# USB-CONN.net
KiCad netlist of a schematic drawn in Altium Designer
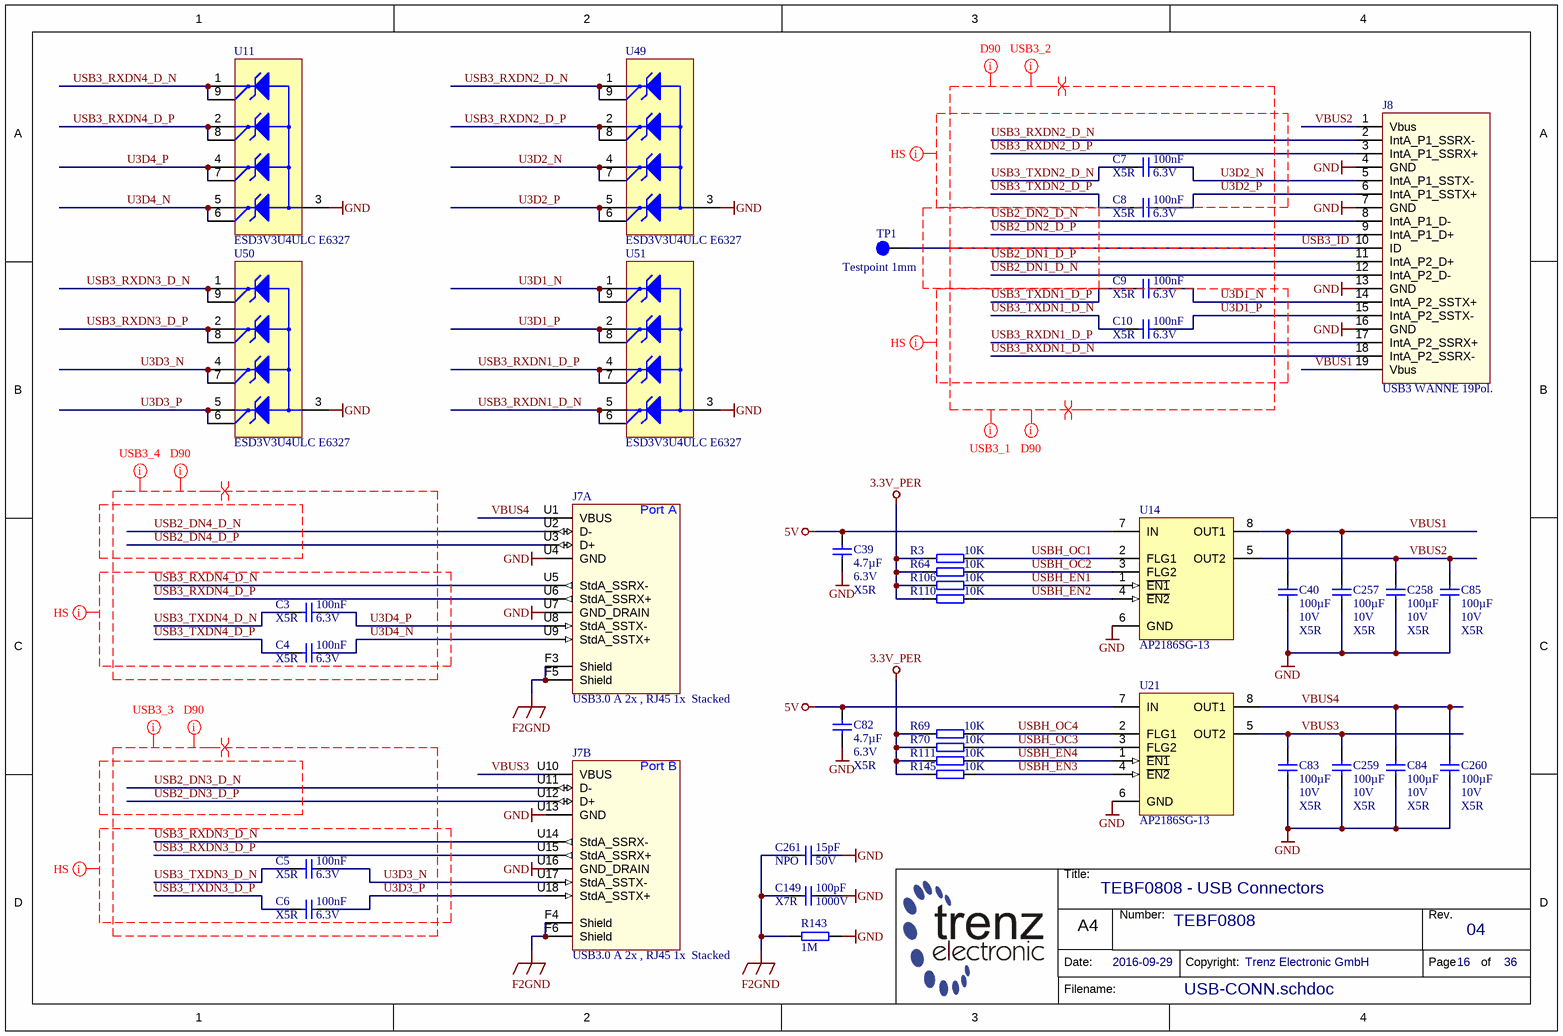
[diagram p0: USB-CONN.schdoc]

(export (version "E")
  (design (tool "Eeschema 10.0.6"))
  (components
    (comp (ref "C3")
      (value "100nF")
      (footprint "CAPC0603X33N")
      (description "KON 100nF 6.3V X5R SMD 10%")
      (fields
        (field (name "VOLTAGE") "6.3V")
        (field (name "TECHNOLOGY") "X5R")
        (field (name "TOLERANCE") "10%")
      )
      (libsource (lib "TE") (part "CAP-NP"))
    )
    (comp (ref "C4")
      (value "100nF")
      (footprint "CAPC0603X33N")
      (description "KON 100nF 6.3V X5R SMD 10%")
      (fields
        (field (name "VOLTAGE") "6.3V")
        (field (name "TECHNOLOGY") "X5R")
        (field (name "TOLERANCE") "10%")
      )
      (libsource (lib "TE") (part "CAP-NP"))
    )
    (comp (ref "C5")
      (value "100nF")
      (footprint "CAPC0603X33N")
      (description "KON 100nF 6.3V X5R SMD 10%")
      (fields
        (field (name "VOLTAGE") "6.3V")
        (field (name "TECHNOLOGY") "X5R")
        (field (name "TOLERANCE") "10%")
      )
      (libsource (lib "TE") (part "CAP-NP"))
    )
    (comp (ref "C6")
      (value "100nF")
      (footprint "CAPC0603X33N")
      (description "KON 100nF 6.3V X5R SMD 10%")
      (fields
        (field (name "VOLTAGE") "6.3V")
        (field (name "TECHNOLOGY") "X5R")
        (field (name "TOLERANCE") "10%")
      )
      (libsource (lib "TE") (part "CAP-NP"))
    )
    (comp (ref "C7")
      (value "100nF")
      (footprint "CAPC0603X33N")
      (description "KON 100nF 6.3V X5R SMD 10%")
      (fields
        (field (name "VOLTAGE") "6.3V")
        (field (name "TECHNOLOGY") "X5R")
        (field (name "TOLERANCE") "10%")
      )
      (libsource (lib "TE") (part "CAP-NP"))
    )
    (comp (ref "C8")
      (value "100nF")
      (footprint "CAPC0603X33N")
      (description "KON 100nF 6.3V X5R SMD 10%")
      (fields
        (field (name "VOLTAGE") "6.3V")
        (field (name "TECHNOLOGY") "X5R")
        (field (name "TOLERANCE") "10%")
      )
      (libsource (lib "TE") (part "CAP-NP"))
    )
    (comp (ref "C9")
      (value "100nF")
      (footprint "CAPC0603X33N")
      (description "KON 100nF 6.3V X5R SMD 10%")
      (fields
        (field (name "VOLTAGE") "6.3V")
        (field (name "TECHNOLOGY") "X5R")
        (field (name "TOLERANCE") "10%")
      )
      (libsource (lib "TE") (part "CAP-NP"))
    )
    (comp (ref "C10")
      (value "100nF")
      (footprint "CAPC0603X33N")
      (description "KON 100nF 6.3V X5R SMD 10%")
      (fields
        (field (name "VOLTAGE") "6.3V")
        (field (name "TECHNOLOGY") "X5R")
        (field (name "TOLERANCE") "10%")
      )
      (libsource (lib "TE") (part "CAP-NP"))
    )
    (comp (ref "C39")
      (value "4.7µF")
      (footprint "CAPC1005X60N")
      (description "KON 4.7µF 6.3V X5R SMD 20%")
      (fields
        (field (name "VOLTAGE") "6.3V")
        (field (name "TECHNOLOGY") "X5R")
        (field (name "TOLERANCE") "20%")
      )
      (libsource (lib "TE") (part "CAP-NP"))
    )
    (comp (ref "C40")
      (value "100µF")
      (footprint "CAPC3216X180N")
      (description "KON 100µF 10V X5R SMD 20%")
      (fields
        (field (name "VOLTAGE") "10V")
        (field (name "TECHNOLOGY") "X5R")
        (field (name "TOLERANCE") "20%")
      )
      (libsource (lib "TE") (part "CAP-NP"))
    )
    (comp (ref "C82")
      (value "4.7µF")
      (footprint "CAPC1005X60N")
      (description "KON 4.7µF 6.3V X5R SMD 20%")
      (fields
        (field (name "VOLTAGE") "6.3V")
        (field (name "TECHNOLOGY") "X5R")
        (field (name "TOLERANCE") "20%")
      )
      (libsource (lib "TE") (part "CAP-NP"))
    )
    (comp (ref "C83")
      (value "100µF")
      (footprint "CAPC3216X180N")
      (description "KON 100µF 10V X5R SMD 20%")
      (fields
        (field (name "VOLTAGE") "10V")
        (field (name "TECHNOLOGY") "X5R")
        (field (name "TOLERANCE") "20%")
      )
      (libsource (lib "TE") (part "CAP-NP"))
    )
    (comp (ref "C84")
      (value "100µF")
      (footprint "CAPC3216X180N")
      (description "KON 100µF 10V X5R SMD 20%")
      (fields
        (field (name "VOLTAGE") "10V")
        (field (name "TECHNOLOGY") "X5R")
        (field (name "TOLERANCE") "20%")
      )
      (libsource (lib "TE") (part "CAP-NP"))
    )
    (comp (ref "C85")
      (value "100µF")
      (footprint "CAPC3216X180N")
      (description "KON 100µF 10V X5R SMD 20%")
      (fields
        (field (name "VOLTAGE") "10V")
        (field (name "TECHNOLOGY") "X5R")
        (field (name "TOLERANCE") "20%")
      )
      (libsource (lib "TE") (part "CAP-NP"))
    )
    (comp (ref "C149")
      (value "100pF")
      (footprint "CAPC3216X180N")
      (description "KON 100pF 1000V X7R 10%")
      (fields
        (field (name "VOLTAGE") "X7R")
        (field (name "TECHNOLOGY") "1000V")
        (field (name "TOLERANCE") "10%")
      )
      (libsource (lib "TE") (part "CAP-NP"))
    )
    (comp (ref "C257")
      (value "100µF")
      (footprint "CAPC3216X180N")
      (description "KON 100µF 10V X5R SMD 20%")
      (fields
        (field (name "VOLTAGE") "10V")
        (field (name "TECHNOLOGY") "X5R")
        (field (name "TOLERANCE") "20%")
      )
      (libsource (lib "TE") (part "CAP-NP"))
    )
    (comp (ref "C258")
      (value "100µF")
      (footprint "CAPC3216X180N")
      (description "KON 100µF 10V X5R SMD 20%")
      (fields
        (field (name "VOLTAGE") "10V")
        (field (name "TECHNOLOGY") "X5R")
        (field (name "TOLERANCE") "20%")
      )
      (libsource (lib "TE") (part "CAP-NP"))
    )
    (comp (ref "C259")
      (value "100µF")
      (footprint "CAPC3216X180N")
      (description "KON 100µF 10V X5R SMD 20%")
      (fields
        (field (name "VOLTAGE") "10V")
        (field (name "TECHNOLOGY") "X5R")
        (field (name "TOLERANCE") "20%")
      )
      (libsource (lib "TE") (part "CAP-NP"))
    )
    (comp (ref "C260")
      (value "100µF")
      (footprint "CAPC3216X180N")
      (description "KON 100µF 10V X5R SMD 20%")
      (fields
        (field (name "VOLTAGE") "10V")
        (field (name "TECHNOLOGY") "X5R")
        (field (name "TOLERANCE") "20%")
      )
      (libsource (lib "TE") (part "CAP-NP"))
    )
    (comp (ref "C261")
      (value "15pF")
      (footprint "CAPC1005X55N")
      (description "KON 15pF NPO 50V SMD")
      (fields (field (name "VOLTAGE") "50V") (field (name "TECHNOLOGY") "NPO"))
      (libsource (lib "TE") (part "CAP-NP"))
    )
    (comp (ref "J7")
      (value "USB3.0 A 2x , RJ45 1x  Stacked")
      (footprint "7497110616")
      (libsource (lib "TE") (part "7497110616"))
    )
    (comp (ref "J8")
      (value "USB3 WANNE 19Pol.")
      (footprint "WANNE2mm2R-19_Intel_USB")
      (description "Stiftleiste USB3 Wanne 19polig 0°")
      (libsource (lib "TE") (part "USB3_ICC_A"))
    )
    (comp (ref "R3")
      (value "10K")
      (footprint "RESC1005X40N")
      (description "WID SMD 10K 1% 0,063W")
      (fields (field (name "TOLERANCE") "1%"))
      (libsource (lib "TE") (part "RES"))
    )
    (comp (ref "R64")
      (value "10K")
      (footprint "RESC1005X40N")
      (description "WID SMD 10K 1% 0,063W")
      (fields (field (name "TOLERANCE") "1%"))
      (libsource (lib "TE") (part "RES"))
    )
    (comp (ref "R69")
      (value "10K")
      (footprint "RESC1005X40N")
      (description "WID SMD 10K 1% 0,063W")
      (fields (field (name "TOLERANCE") "1%"))
      (libsource (lib "TE") (part "RES"))
    )
    (comp (ref "R70")
      (value "10K")
      (footprint "RESC1005X40N")
      (description "WID SMD 10K 1% 0,063W")
      (fields (field (name "TOLERANCE") "1%"))
      (libsource (lib "TE") (part "RES"))
    )
    (comp (ref "R106")
      (value "10K")
      (footprint "RESC1005X40N")
      (description "WID SMD 10K 1% 0,063W")
      (fields (field (name "TOLERANCE") "1%"))
      (libsource (lib "TE") (part "RES"))
    )
    (comp (ref "R110")
      (value "10K")
      (footprint "RESC1005X40N")
      (description "WID SMD 10K 1% 0,063W")
      (fields (field (name "TOLERANCE") "1%"))
      (libsource (lib "TE") (part "RES"))
    )
    (comp (ref "R111")
      (value "10K")
      (footprint "RESC1005X40N")
      (description "WID SMD 10K 1% 0,063W")
      (fields (field (name "TOLERANCE") "1%"))
      (libsource (lib "TE") (part "RES"))
    )
    (comp (ref "R143")
      (value "1M")
      (footprint "RESC3216X65N")
      (description "WID SMD 1M 5% 0,25W")
      (fields (field (name "TOLERANCE") "5%"))
      (libsource (lib "TE") (part "RES"))
    )
    (comp (ref "R145")
      (value "10K")
      (footprint "RESC1005X40N")
      (description "WID SMD 10K 1% 0,063W")
      (fields (field (name "TOLERANCE") "1%"))
      (libsource (lib "TE") (part "RES"))
    )
    (comp (ref "TP1") (value "Testpoint 1mm") (footprint "TP_1mm") (libsource (lib "TE") (part "TP")))
    (comp (ref "U11")
      (value "ESD3V3U4ULC E6327")
      (footprint "TSLP-9-1")
      (description "TVS UL Cap. 4xIOs ESD 3.3V")
      (libsource (lib "TE") (part "ESD3V3U4ULC"))
    )
    (comp (ref "U14")
      (value "AP2186SG-13")
      (footprint "SOIC127P600X175-8N")
      (libsource (lib "TE") (part "AP2186"))
    )
    (comp (ref "U21")
      (value "AP2186SG-13")
      (footprint "SOIC127P600X175-8N")
      (libsource (lib "TE") (part "AP2186"))
    )
    (comp (ref "U49")
      (value "ESD3V3U4ULC E6327")
      (footprint "TSLP-9-1")
      (description "TVS UL Cap. 4xIOs ESD 3.3V")
      (libsource (lib "TE") (part "ESD3V3U4ULC"))
    )
    (comp (ref "U50")
      (value "ESD3V3U4ULC E6327")
      (footprint "TSLP-9-1")
      (description "TVS UL Cap. 4xIOs ESD 3.3V")
      (libsource (lib "TE") (part "ESD3V3U4ULC"))
    )
    (comp (ref "U51")
      (value "ESD3V3U4ULC E6327")
      (footprint "TSLP-9-1")
      (description "TVS UL Cap. 4xIOs ESD 3.3V")
      (libsource (lib "TE") (part "ESD3V3U4ULC"))
    )
  )
  (nets
    (net (code "1") (name "/U3D1_N") (class "Default")
      (node (ref "C9") (pin "2") (pinfunction "2_2") (pintype "passive"))
      (node (ref "J8") (pin "14") (pinfunction "IntA_P2_SSTX+_14") (pintype "passive"))
      (node (ref "U51") (pin "1") (pinfunction "1_1") (pintype "passive"))
      (node (ref "U51") (pin "9") (pinfunction "9_9") (pintype "passive"))
    )
    (net (code "2") (name "/U3D1_P") (class "Default")
      (node (ref "C10") (pin "2") (pinfunction "2_2") (pintype "passive"))
      (node (ref "J8") (pin "15") (pinfunction "IntA_P2_SSTX-_15") (pintype "passive"))
      (node (ref "U51") (pin "2") (pinfunction "2_2") (pintype "passive"))
      (node (ref "U51") (pin "8") (pinfunction "8_8") (pintype "passive"))
    )
    (net (code "3") (name "/U3D2_N") (class "Default")
      (node (ref "C7") (pin "2") (pinfunction "2_2") (pintype "passive"))
      (node (ref "J8") (pin "5") (pinfunction "IntA_P1_SSTX-_5") (pintype "passive"))
      (node (ref "U49") (pin "4") (pinfunction "4_4") (pintype "passive"))
      (node (ref "U49") (pin "7") (pinfunction "7_7") (pintype "passive"))
    )
    (net (code "4") (name "/U3D2_P") (class "Default")
      (node (ref "C8") (pin "2") (pinfunction "2_2") (pintype "passive"))
      (node (ref "J8") (pin "6") (pinfunction "IntA_P1_SSTX+_6") (pintype "passive"))
      (node (ref "U49") (pin "5") (pinfunction "5_5") (pintype "passive"))
      (node (ref "U49") (pin "6") (pinfunction "6_6") (pintype "passive"))
    )
    (net (code "5") (name "/U3D3_N") (class "Default")
      (node (ref "C5") (pin "2") (pinfunction "2_2") (pintype "passive"))
      (node (ref "J7") (pin "U17") (pinfunction "StdA_SSTX-_U17") (pintype "input"))
      (node (ref "U50") (pin "4") (pinfunction "4_4") (pintype "passive"))
      (node (ref "U50") (pin "7") (pinfunction "7_7") (pintype "passive"))
    )
    (net (code "6") (name "/U3D3_P") (class "Default")
      (node (ref "C6") (pin "2") (pinfunction "2_2") (pintype "passive"))
      (node (ref "J7") (pin "U18") (pinfunction "StdA_SSTX+_U18") (pintype "input"))
      (node (ref "U50") (pin "5") (pinfunction "5_5") (pintype "passive"))
      (node (ref "U50") (pin "6") (pinfunction "6_6") (pintype "passive"))
    )
    (net (code "7") (name "/U3D4_N") (class "Default")
      (node (ref "C4") (pin "2") (pinfunction "2_2") (pintype "passive"))
      (node (ref "J7") (pin "U9") (pinfunction "StdA_SSTX+_U9") (pintype "input"))
      (node (ref "U11") (pin "5") (pinfunction "5_5") (pintype "passive"))
      (node (ref "U11") (pin "6") (pinfunction "6_6") (pintype "passive"))
    )
    (net (code "8") (name "/U3D4_P") (class "Default")
      (node (ref "C3") (pin "2") (pinfunction "2_2") (pintype "passive"))
      (node (ref "J7") (pin "U8") (pinfunction "StdA_SSTX-_U8") (pintype "input"))
      (node (ref "U11") (pin "4") (pinfunction "4_4") (pintype "passive"))
      (node (ref "U11") (pin "7") (pinfunction "7_7") (pintype "passive"))
    )
    (net (code "9") (name "/USB2_DN1_D_N") (class "Default")
      (node (ref "J8") (pin "12") (pinfunction "IntA_P2_D-_12") (pintype "passive"))
    )
    (net (code "10") (name "/USB2_DN1_D_P") (class "Default")
      (node (ref "J8") (pin "11") (pinfunction "IntA_P2_D+_11") (pintype "passive"))
    )
    (net (code "11") (name "/USB2_DN2_D_N") (class "Default")
      (node (ref "J8") (pin "8") (pinfunction "IntA_P1_D-_8") (pintype "passive"))
    )
    (net (code "12") (name "/USB2_DN2_D_P") (class "Default")
      (node (ref "J8") (pin "9") (pinfunction "IntA_P1_D+_9") (pintype "passive"))
    )
    (net (code "13") (name "/USB2_DN3_D_N") (class "Default")
      (node (ref "J7") (pin "U11") (pinfunction "D-_U11") (pintype "bidirectional"))
    )
    (net (code "14") (name "/USB2_DN3_D_P") (class "Default")
      (node (ref "J7") (pin "U12") (pinfunction "D+_U12") (pintype "bidirectional"))
    )
    (net (code "15") (name "/USB2_DN4_D_N") (class "Default")
      (node (ref "J7") (pin "U2") (pinfunction "D-_U2") (pintype "bidirectional"))
    )
    (net (code "16") (name "/USB2_DN4_D_P") (class "Default")
      (node (ref "J7") (pin "U3") (pinfunction "D+_U3") (pintype "bidirectional"))
    )
    (net (code "17") (name "/USB3_ID") (class "Default")
      (node (ref "J8") (pin "10") (pinfunction "ID_10") (pintype "passive"))
      (node (ref "TP1") (pin "1") (pintype "passive"))
    )
    (net (code "18") (name "/USB3_RXDN1_D_N") (class "Default")
      (node (ref "J8") (pin "18") (pinfunction "IntA_P2_SSRX-_18") (pintype "passive"))
      (node (ref "U51") (pin "5") (pinfunction "5_5") (pintype "passive"))
      (node (ref "U51") (pin "6") (pinfunction "6_6") (pintype "passive"))
    )
    (net (code "19") (name "/USB3_RXDN1_D_P") (class "Default")
      (node (ref "J8") (pin "17") (pinfunction "IntA_P2_SSRX+_17") (pintype "passive"))
      (node (ref "U51") (pin "4") (pinfunction "4_4") (pintype "passive"))
      (node (ref "U51") (pin "7") (pinfunction "7_7") (pintype "passive"))
    )
    (net (code "20") (name "/USB3_RXDN2_D_N") (class "Default")
      (node (ref "J8") (pin "2") (pinfunction "IntA_P1_SSRX-_2") (pintype "passive"))
      (node (ref "U49") (pin "1") (pinfunction "1_1") (pintype "passive"))
      (node (ref "U49") (pin "9") (pinfunction "9_9") (pintype "passive"))
    )
    (net (code "21") (name "/USB3_RXDN2_D_P") (class "Default")
      (node (ref "J8") (pin "3") (pinfunction "IntA_P1_SSRX+_3") (pintype "passive"))
      (node (ref "U49") (pin "2") (pinfunction "2_2") (pintype "passive"))
      (node (ref "U49") (pin "8") (pinfunction "8_8") (pintype "passive"))
    )
    (net (code "22") (name "/USB3_RXDN3_D_N") (class "Default")
      (node (ref "J7") (pin "U14") (pinfunction "StdA_SSRX-_U14") (pintype "output"))
      (node (ref "U50") (pin "1") (pinfunction "1_1") (pintype "passive"))
      (node (ref "U50") (pin "9") (pinfunction "9_9") (pintype "passive"))
    )
    (net (code "23") (name "/USB3_RXDN3_D_P") (class "Default")
      (node (ref "J7") (pin "U15") (pinfunction "StdA_SSRX+_U15") (pintype "output"))
      (node (ref "U50") (pin "2") (pinfunction "2_2") (pintype "passive"))
      (node (ref "U50") (pin "8") (pinfunction "8_8") (pintype "passive"))
    )
    (net (code "24") (name "/USB3_RXDN4_D_N") (class "Default")
      (node (ref "J7") (pin "U5") (pinfunction "StdA_SSRX-_U5") (pintype "output"))
      (node (ref "U11") (pin "1") (pinfunction "1_1") (pintype "passive"))
      (node (ref "U11") (pin "9") (pinfunction "9_9") (pintype "passive"))
    )
    (net (code "25") (name "/USB3_RXDN4_D_P") (class "Default")
      (node (ref "J7") (pin "U6") (pinfunction "StdA_SSRX+_U6") (pintype "output"))
      (node (ref "U11") (pin "2") (pinfunction "2_2") (pintype "passive"))
      (node (ref "U11") (pin "8") (pinfunction "8_8") (pintype "passive"))
    )
    (net (code "26") (name "/USB3_TXDN1_D_N") (class "Default")
      (node (ref "C10") (pin "1") (pinfunction "1_1") (pintype "passive"))
    )
    (net (code "27") (name "/USB3_TXDN1_D_P") (class "Default")
      (node (ref "C9") (pin "1") (pinfunction "1_1") (pintype "passive"))
    )
    (net (code "28") (name "/USB3_TXDN2_D_N") (class "Default")
      (node (ref "C7") (pin "1") (pinfunction "1_1") (pintype "passive"))
    )
    (net (code "29") (name "/USB3_TXDN2_D_P") (class "Default")
      (node (ref "C8") (pin "1") (pinfunction "1_1") (pintype "passive"))
    )
    (net (code "30") (name "/USB3_TXDN3_D_N") (class "Default")
      (node (ref "C5") (pin "1") (pinfunction "1_1") (pintype "passive"))
    )
    (net (code "31") (name "/USB3_TXDN3_D_P") (class "Default")
      (node (ref "C6") (pin "1") (pinfunction "1_1") (pintype "passive"))
    )
    (net (code "32") (name "/USB3_TXDN4_D_N") (class "Default")
      (node (ref "C3") (pin "1") (pinfunction "1_1") (pintype "passive"))
    )
    (net (code "33") (name "/USB3_TXDN4_D_P") (class "Default")
      (node (ref "C4") (pin "1") (pinfunction "1_1") (pintype "passive"))
    )
    (net (code "34") (name "/USBH_EN1") (class "Default")
      (node (ref "R106") (pin "2") (pinfunction "2_2") (pintype "passive"))
      (node (ref "U14") (pin "1") (pinfunction "~{EN1}_1") (pintype "input"))
    )
    (net (code "35") (name "/USBH_EN2") (class "Default")
      (node (ref "R110") (pin "2") (pinfunction "2_2") (pintype "passive"))
      (node (ref "U14") (pin "4") (pinfunction "~{EN2}_4") (pintype "input"))
    )
    (net (code "36") (name "/USBH_EN3") (class "Default")
      (node (ref "R145") (pin "2") (pinfunction "2_2") (pintype "passive"))
      (node (ref "U21") (pin "4") (pinfunction "~{EN2}_4") (pintype "input"))
    )
    (net (code "37") (name "/USBH_EN4") (class "Default")
      (node (ref "R111") (pin "2") (pinfunction "2_2") (pintype "passive"))
      (node (ref "U21") (pin "1") (pinfunction "~{EN1}_1") (pintype "input"))
    )
    (net (code "38") (name "/USBH_OC1") (class "Default")
      (node (ref "R3") (pin "2") (pinfunction "2_2") (pintype "passive"))
      (node (ref "U14") (pin "2") (pinfunction "FLG1_2") (pintype "passive"))
    )
    (net (code "39") (name "/USBH_OC2") (class "Default")
      (node (ref "R64") (pin "2") (pinfunction "2_2") (pintype "passive"))
      (node (ref "U14") (pin "3") (pinfunction "FLG2_3") (pintype "passive"))
    )
    (net (code "40") (name "/USBH_OC3") (class "Default")
      (node (ref "R70") (pin "2") (pinfunction "2_2") (pintype "passive"))
      (node (ref "U21") (pin "3") (pinfunction "FLG2_3") (pintype "passive"))
    )
    (net (code "41") (name "/USBH_OC4") (class "Default")
      (node (ref "R69") (pin "2") (pinfunction "2_2") (pintype "passive"))
      (node (ref "U21") (pin "2") (pinfunction "FLG1_2") (pintype "passive"))
    )
    (net (code "42") (name "/VBUS1") (class "Default")
      (node (ref "C257") (pin "1") (pinfunction "1_1") (pintype "passive"))
      (node (ref "C40") (pin "1") (pinfunction "1_1") (pintype "passive"))
      (node (ref "J8") (pin "19") (pinfunction "Vbus_19") (pintype "passive"))
      (node (ref "U14") (pin "8") (pinfunction "OUT1_8") (pintype "power_in"))
    )
    (net (code "43") (name "/VBUS2") (class "Default")
      (node (ref "C258") (pin "1") (pinfunction "1_1") (pintype "passive"))
      (node (ref "C85") (pin "1") (pinfunction "1_1") (pintype "passive"))
      (node (ref "J8") (pin "1") (pinfunction "Vbus_1") (pintype "passive"))
      (node (ref "U14") (pin "5") (pinfunction "OUT2_5") (pintype "power_in"))
    )
    (net (code "44") (name "/VBUS3") (class "Default")
      (node (ref "C259") (pin "1") (pinfunction "1_1") (pintype "passive"))
      (node (ref "C83") (pin "1") (pinfunction "1_1") (pintype "passive"))
      (node (ref "J7") (pin "U10") (pinfunction "VBUS_U10") (pintype "power_in"))
      (node (ref "U21") (pin "5") (pinfunction "OUT2_5") (pintype "power_in"))
    )
    (net (code "45") (name "/VBUS4") (class "Default")
      (node (ref "C260") (pin "1") (pinfunction "1_1") (pintype "passive"))
      (node (ref "C84") (pin "1") (pinfunction "1_1") (pintype "passive"))
      (node (ref "J7") (pin "U1") (pinfunction "VBUS_U1") (pintype "power_in"))
      (node (ref "U21") (pin "8") (pinfunction "OUT1_8") (pintype "power_in"))
    )
    (net (code "46") (name "3.3V_PER") (class "Default")
      (node (ref "R106") (pin "1") (pinfunction "1_1") (pintype "passive"))
      (node (ref "R110") (pin "1") (pinfunction "1_1") (pintype "passive"))
      (node (ref "R111") (pin "1") (pinfunction "1_1") (pintype "passive"))
      (node (ref "R145") (pin "1") (pinfunction "1_1") (pintype "passive"))
      (node (ref "R3") (pin "1") (pinfunction "1_1") (pintype "passive"))
      (node (ref "R64") (pin "1") (pinfunction "1_1") (pintype "passive"))
      (node (ref "R69") (pin "1") (pinfunction "1_1") (pintype "passive"))
      (node (ref "R70") (pin "1") (pinfunction "1_1") (pintype "passive"))
    )
    (net (code "47") (name "5V") (class "Default")
      (node (ref "C39") (pin "1") (pinfunction "1_1") (pintype "passive"))
      (node (ref "C82") (pin "1") (pinfunction "1_1") (pintype "passive"))
      (node (ref "U14") (pin "7") (pinfunction "IN_7") (pintype "power_in"))
      (node (ref "U21") (pin "7") (pinfunction "IN_7") (pintype "power_in"))
    )
    (net (code "48") (name "F2GND") (class "Default")
      (node (ref "C149") (pin "1") (pinfunction "1_1") (pintype "passive"))
      (node (ref "C261") (pin "1") (pinfunction "1_1") (pintype "passive"))
      (node (ref "J7") (pin "F3") (pinfunction "Shield_F3") (pintype "passive"))
      (node (ref "J7") (pin "F4") (pinfunction "Shield_F4") (pintype "passive"))
      (node (ref "J7") (pin "F5") (pinfunction "Shield_F5") (pintype "passive"))
      (node (ref "J7") (pin "F6") (pinfunction "Shield_F6") (pintype "passive"))
      (node (ref "R143") (pin "1") (pinfunction "1_1") (pintype "passive"))
    )
    (net (code "49") (name "GND") (class "Default")
      (node (ref "C149") (pin "2") (pinfunction "2_2") (pintype "passive"))
      (node (ref "C257") (pin "2") (pinfunction "2_2") (pintype "passive"))
      (node (ref "C258") (pin "2") (pinfunction "2_2") (pintype "passive"))
      (node (ref "C259") (pin "2") (pinfunction "2_2") (pintype "passive"))
      (node (ref "C260") (pin "2") (pinfunction "2_2") (pintype "passive"))
      (node (ref "C261") (pin "2") (pinfunction "2_2") (pintype "passive"))
      (node (ref "C39") (pin "2") (pinfunction "2_2") (pintype "passive"))
      (node (ref "C40") (pin "2") (pinfunction "2_2") (pintype "passive"))
      (node (ref "C82") (pin "2") (pinfunction "2_2") (pintype "passive"))
      (node (ref "C83") (pin "2") (pinfunction "2_2") (pintype "passive"))
      (node (ref "C84") (pin "2") (pinfunction "2_2") (pintype "passive"))
      (node (ref "C85") (pin "2") (pinfunction "2_2") (pintype "passive"))
      (node (ref "J7") (pin "U13") (pinfunction "GND_U13") (pintype "power_in"))
      (node (ref "J7") (pin "U16") (pinfunction "GND_DRAIN_U16") (pintype "power_in"))
      (node (ref "J7") (pin "U4") (pinfunction "GND_U4") (pintype "power_in"))
      (node (ref "J7") (pin "U7") (pinfunction "GND_DRAIN_U7") (pintype "power_in"))
      (node (ref "J8") (pin "13") (pinfunction "GND_13") (pintype "passive"))
      (node (ref "J8") (pin "16") (pinfunction "GND_16") (pintype "passive"))
      (node (ref "J8") (pin "4") (pinfunction "GND_4") (pintype "passive"))
      (node (ref "J8") (pin "7") (pinfunction "GND_7") (pintype "passive"))
      (node (ref "R143") (pin "2") (pinfunction "2_2") (pintype "passive"))
      (node (ref "U11") (pin "3") (pinfunction "3_3") (pintype "passive"))
      (node (ref "U14") (pin "6") (pinfunction "GND_6") (pintype "power_in"))
      (node (ref "U21") (pin "6") (pinfunction "GND_6") (pintype "power_in"))
      (node (ref "U49") (pin "3") (pinfunction "3_3") (pintype "passive"))
      (node (ref "U50") (pin "3") (pinfunction "3_3") (pintype "passive"))
      (node (ref "U51") (pin "3") (pinfunction "3_3") (pintype "passive"))
    )
  )
)
